# HID-Bridge-FTDI_proto.net
KiCad netlist of a schematic drawn in EAGLE
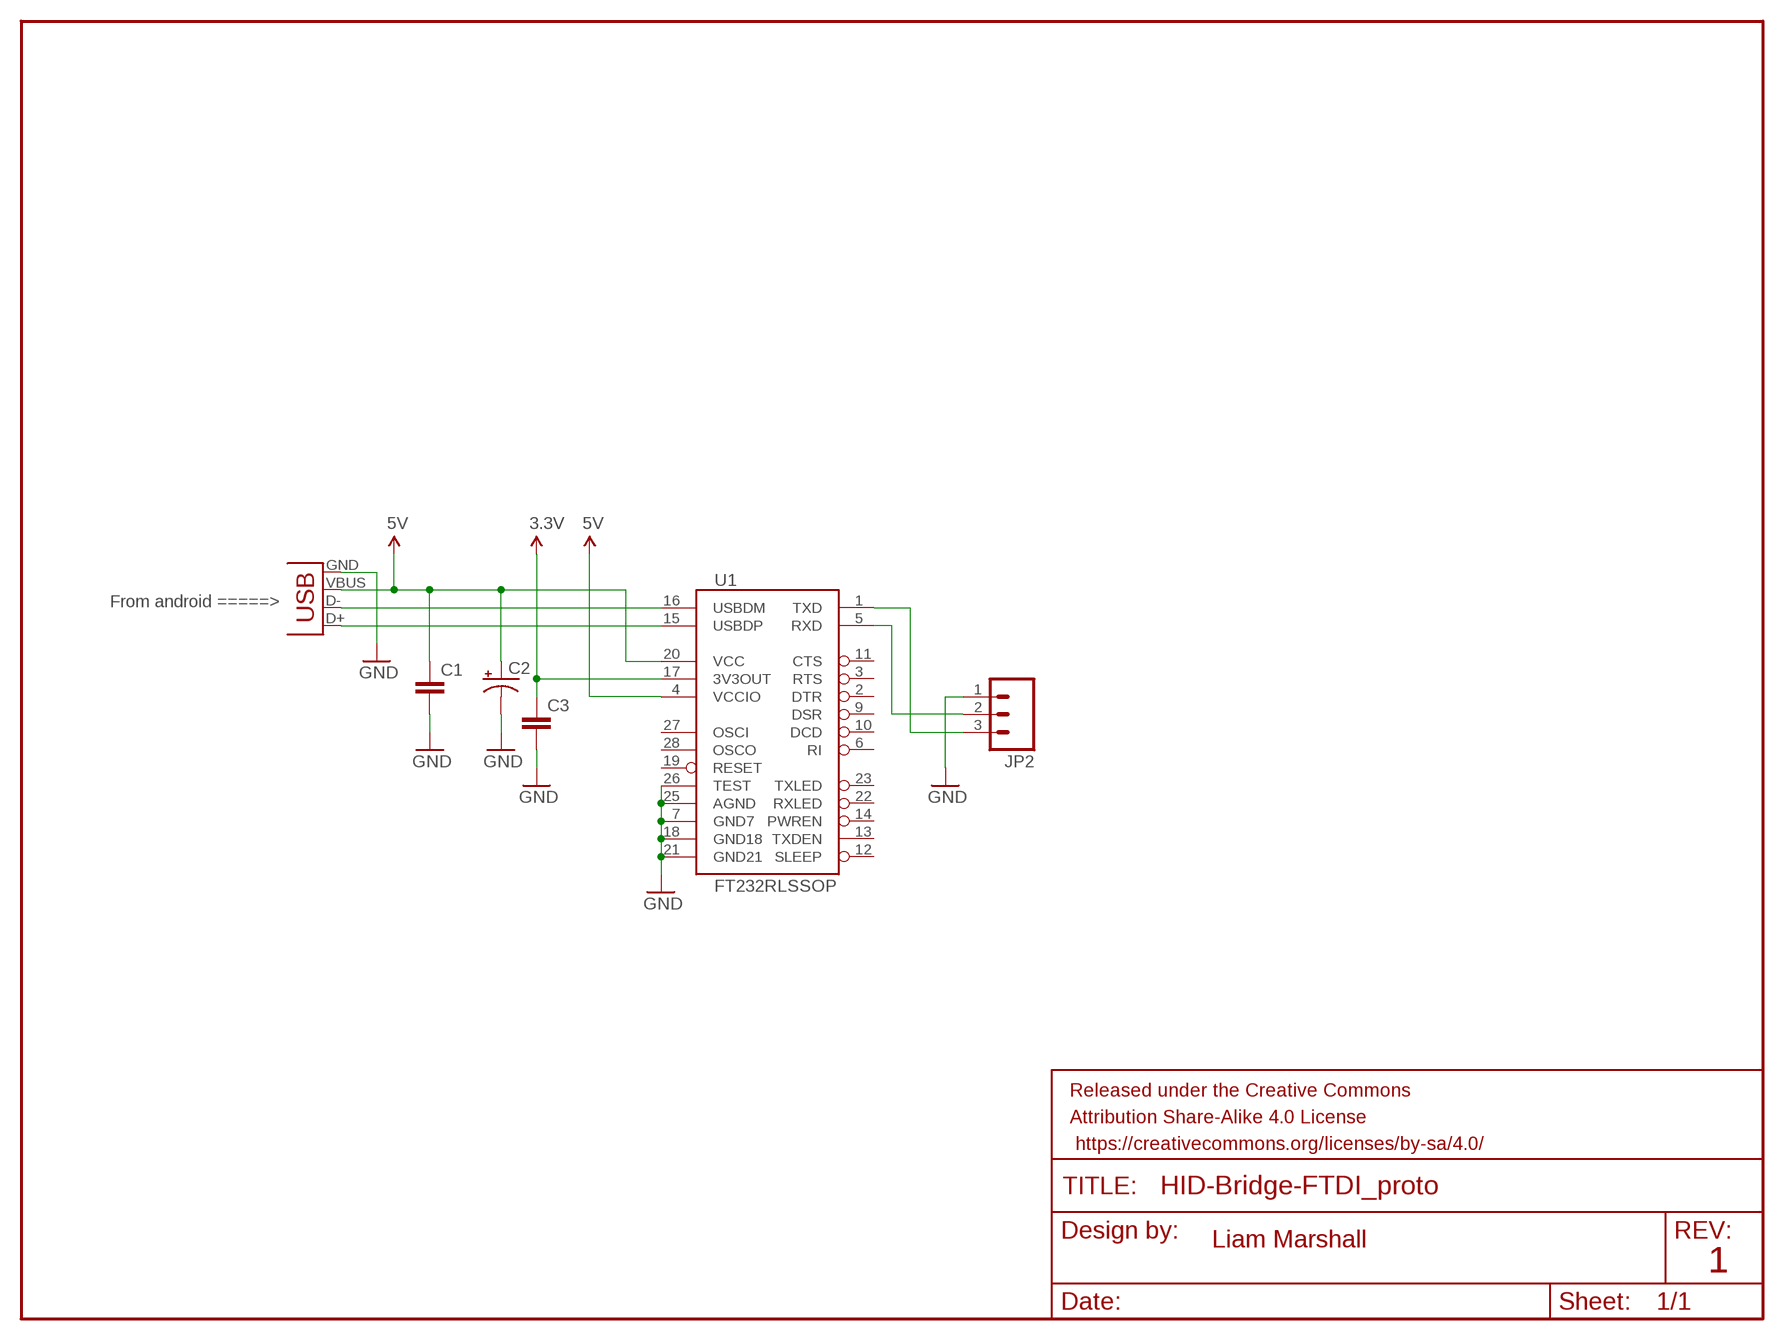
[diagram p0: schematic, sheet 1]

(export (version "E")
  (design (tool "Eeschema 10.0.6"))
  (components
    (comp (ref "C1")
      (value "0.1UF-50V-20%(PTH)KIT-EZ")
      (footprint "eagle-import:CAP-PTH-SMALL-KIT")
      (libsource (lib "eagle-import") (part "0.1UF-50V-20%(PTH)KIT-EZ"))
    )
    (comp (ref "C2")
      (value "10UF-25V-20%(PTH)")
      (footprint "eagle-import:CPOL-RADIAL-10UF-25V")
      (libsource (lib "eagle-import") (part "10UF-25V-20%(PTH)"))
    )
    (comp (ref "C3")
      (value "0.1UF-50V-20%(PTH)KIT-EZ")
      (footprint "eagle-import:CAP-PTH-SMALL-KIT")
      (libsource (lib "eagle-import") (part "0.1UF-50V-20%(PTH)KIT-EZ"))
    )
    (comp (ref "FRAME1")
      (value "FRAME-LETTER")
      (footprint "eagle-import:CREATIVE_COMMONS")
      (libsource (lib "eagle-import") (part "FRAME-LETTER"))
    )
    (comp (ref "JP1")
      (value "USB-B")
      (footprint "eagle-import:USB-B-PTH")
      (libsource (lib "eagle-import") (part "USBPTH"))
    )
    (comp (ref "JP2")
      (value "M03PTH")
      (footprint "eagle-import:1X03")
      (libsource (lib "eagle-import") (part "M03PTH"))
    )
    (comp (ref "U1")
      (value "FT232RLSSOP")
      (footprint "eagle-import:SSOP28DB")
      (libsource (lib "eagle-import") (part "FT232RLSSOP"))
    )
  )
  (nets
    (net (code "1") (name "3.3V") (class "Default")
      (node (ref "C3") (pin "1") (pinfunction "1_1") (pintype "passive"))
      (node (ref "U1") (pin "17") (pinfunction "3V3OUT_17") (pintype "output"))
    )
    (net (code "2") (name "5V") (class "Default")
      (node (ref "C1") (pin "1") (pinfunction "1_1") (pintype "passive"))
      (node (ref "C2") (pin "1") (pinfunction "+_1") (pintype "passive"))
      (node (ref "JP1") (pin "VBUS") (pinfunction "VBUS_VBUS") (pintype "bidirectional"))
      (node (ref "U1") (pin "20") (pinfunction "VCC_20") (pintype "power_in"))
      (node (ref "U1") (pin "4") (pinfunction "VCCIO_4") (pintype "power_in"))
    )
    (net (code "3") (name "GND") (class "Default")
      (node (ref "C1") (pin "2") (pinfunction "2_2") (pintype "passive"))
      (node (ref "C2") (pin "2") (pinfunction "-_2") (pintype "passive"))
      (node (ref "C3") (pin "2") (pinfunction "2_2") (pintype "passive"))
      (node (ref "JP1") (pin "GND") (pinfunction "GND_GND") (pintype "bidirectional"))
      (node (ref "JP2") (pin "1") (pinfunction "1_1") (pintype "passive"))
      (node (ref "U1") (pin "18") (pinfunction "GND18_18") (pintype "power_in"))
      (node (ref "U1") (pin "21") (pinfunction "GND21_21") (pintype "power_in"))
      (node (ref "U1") (pin "25") (pinfunction "AGND_25") (pintype "power_in"))
      (node (ref "U1") (pin "26") (pinfunction "TEST_26") (pintype "input"))
      (node (ref "U1") (pin "7") (pinfunction "GND7_7") (pintype "power_in"))
    )
    (net (code "4") (name "Net-(U1-RXD)") (class "Default")
      (node (ref "JP2") (pin "2") (pinfunction "2_2") (pintype "passive"))
      (node (ref "U1") (pin "5") (pinfunction "RXD_5") (pintype "input"))
    )
    (net (code "5") (name "Net-(U1-TXD)") (class "Default")
      (node (ref "JP2") (pin "3") (pinfunction "3_3") (pintype "passive"))
      (node (ref "U1") (pin "1") (pinfunction "TXD_1") (pintype "output"))
    )
    (net (code "6") (name "Net-(U1-USBDM)") (class "Default")
      (node (ref "JP1") (pin "D-") (pinfunction "D-_D-") (pintype "bidirectional"))
      (node (ref "U1") (pin "16") (pinfunction "USBDM_16") (pintype "bidirectional"))
    )
    (net (code "7") (name "Net-(U1-USBDP)") (class "Default")
      (node (ref "JP1") (pin "D+") (pinfunction "D+_D+") (pintype "bidirectional"))
      (node (ref "U1") (pin "15") (pinfunction "USBDP_15") (pintype "bidirectional"))
    )
    (net (code "8") (name "unconnected-(U1-CTS-Pad11)") (class "Default")
      (node (ref "U1") (pin "11") (pinfunction "CTS_11") (pintype "input"))
    )
    (net (code "9") (name "unconnected-(U1-DCD-Pad10)") (class "Default")
      (node (ref "U1") (pin "10") (pinfunction "DCD_10") (pintype "input"))
    )
    (net (code "10") (name "unconnected-(U1-DSR-Pad9)") (class "Default")
      (node (ref "U1") (pin "9") (pinfunction "DSR_9") (pintype "input"))
    )
    (net (code "11") (name "unconnected-(U1-DTR-Pad2)") (class "Default")
      (node (ref "U1") (pin "2") (pinfunction "DTR_2") (pintype "output"))
    )
    (net (code "12") (name "unconnected-(U1-OSCI-Pad27)") (class "Default")
      (node (ref "U1") (pin "27") (pinfunction "OSCI_27") (pintype "input"))
    )
    (net (code "13") (name "unconnected-(U1-OSCO-Pad28)") (class "Default")
      (node (ref "U1") (pin "28") (pinfunction "OSCO_28") (pintype "output"))
    )
    (net (code "14") (name "unconnected-(U1-PWREN-Pad14)") (class "Default")
      (node (ref "U1") (pin "14") (pinfunction "PWREN_14") (pintype "input"))
    )
    (net (code "15") (name "unconnected-(U1-RESET-Pad19)") (class "Default")
      (node (ref "U1") (pin "19") (pinfunction "RESET_19") (pintype "input"))
    )
    (net (code "16") (name "unconnected-(U1-RI-Pad6)") (class "Default")
      (node (ref "U1") (pin "6") (pinfunction "RI_6") (pintype "input"))
    )
    (net (code "17") (name "unconnected-(U1-RTS-Pad3)") (class "Default")
      (node (ref "U1") (pin "3") (pinfunction "RTS_3") (pintype "output"))
    )
    (net (code "18") (name "unconnected-(U1-RXLED-Pad22)") (class "Default")
      (node (ref "U1") (pin "22") (pinfunction "RXLED_22") (pintype "input"))
    )
    (net (code "19") (name "unconnected-(U1-SLEEP-Pad12)") (class "Default")
      (node (ref "U1") (pin "12") (pinfunction "SLEEP_12") (pintype "input"))
    )
    (net (code "20") (name "unconnected-(U1-TXDEN-Pad13)") (class "Default")
      (node (ref "U1") (pin "13") (pinfunction "TXDEN_13") (pintype "input"))
    )
    (net (code "21") (name "unconnected-(U1-TXLED-Pad23)") (class "Default")
      (node (ref "U1") (pin "23") (pinfunction "TXLED_23") (pintype "input"))
    )
  )
)
